# DesignPCB.net
KiCad netlist of a schematic drawn in EasyEDA
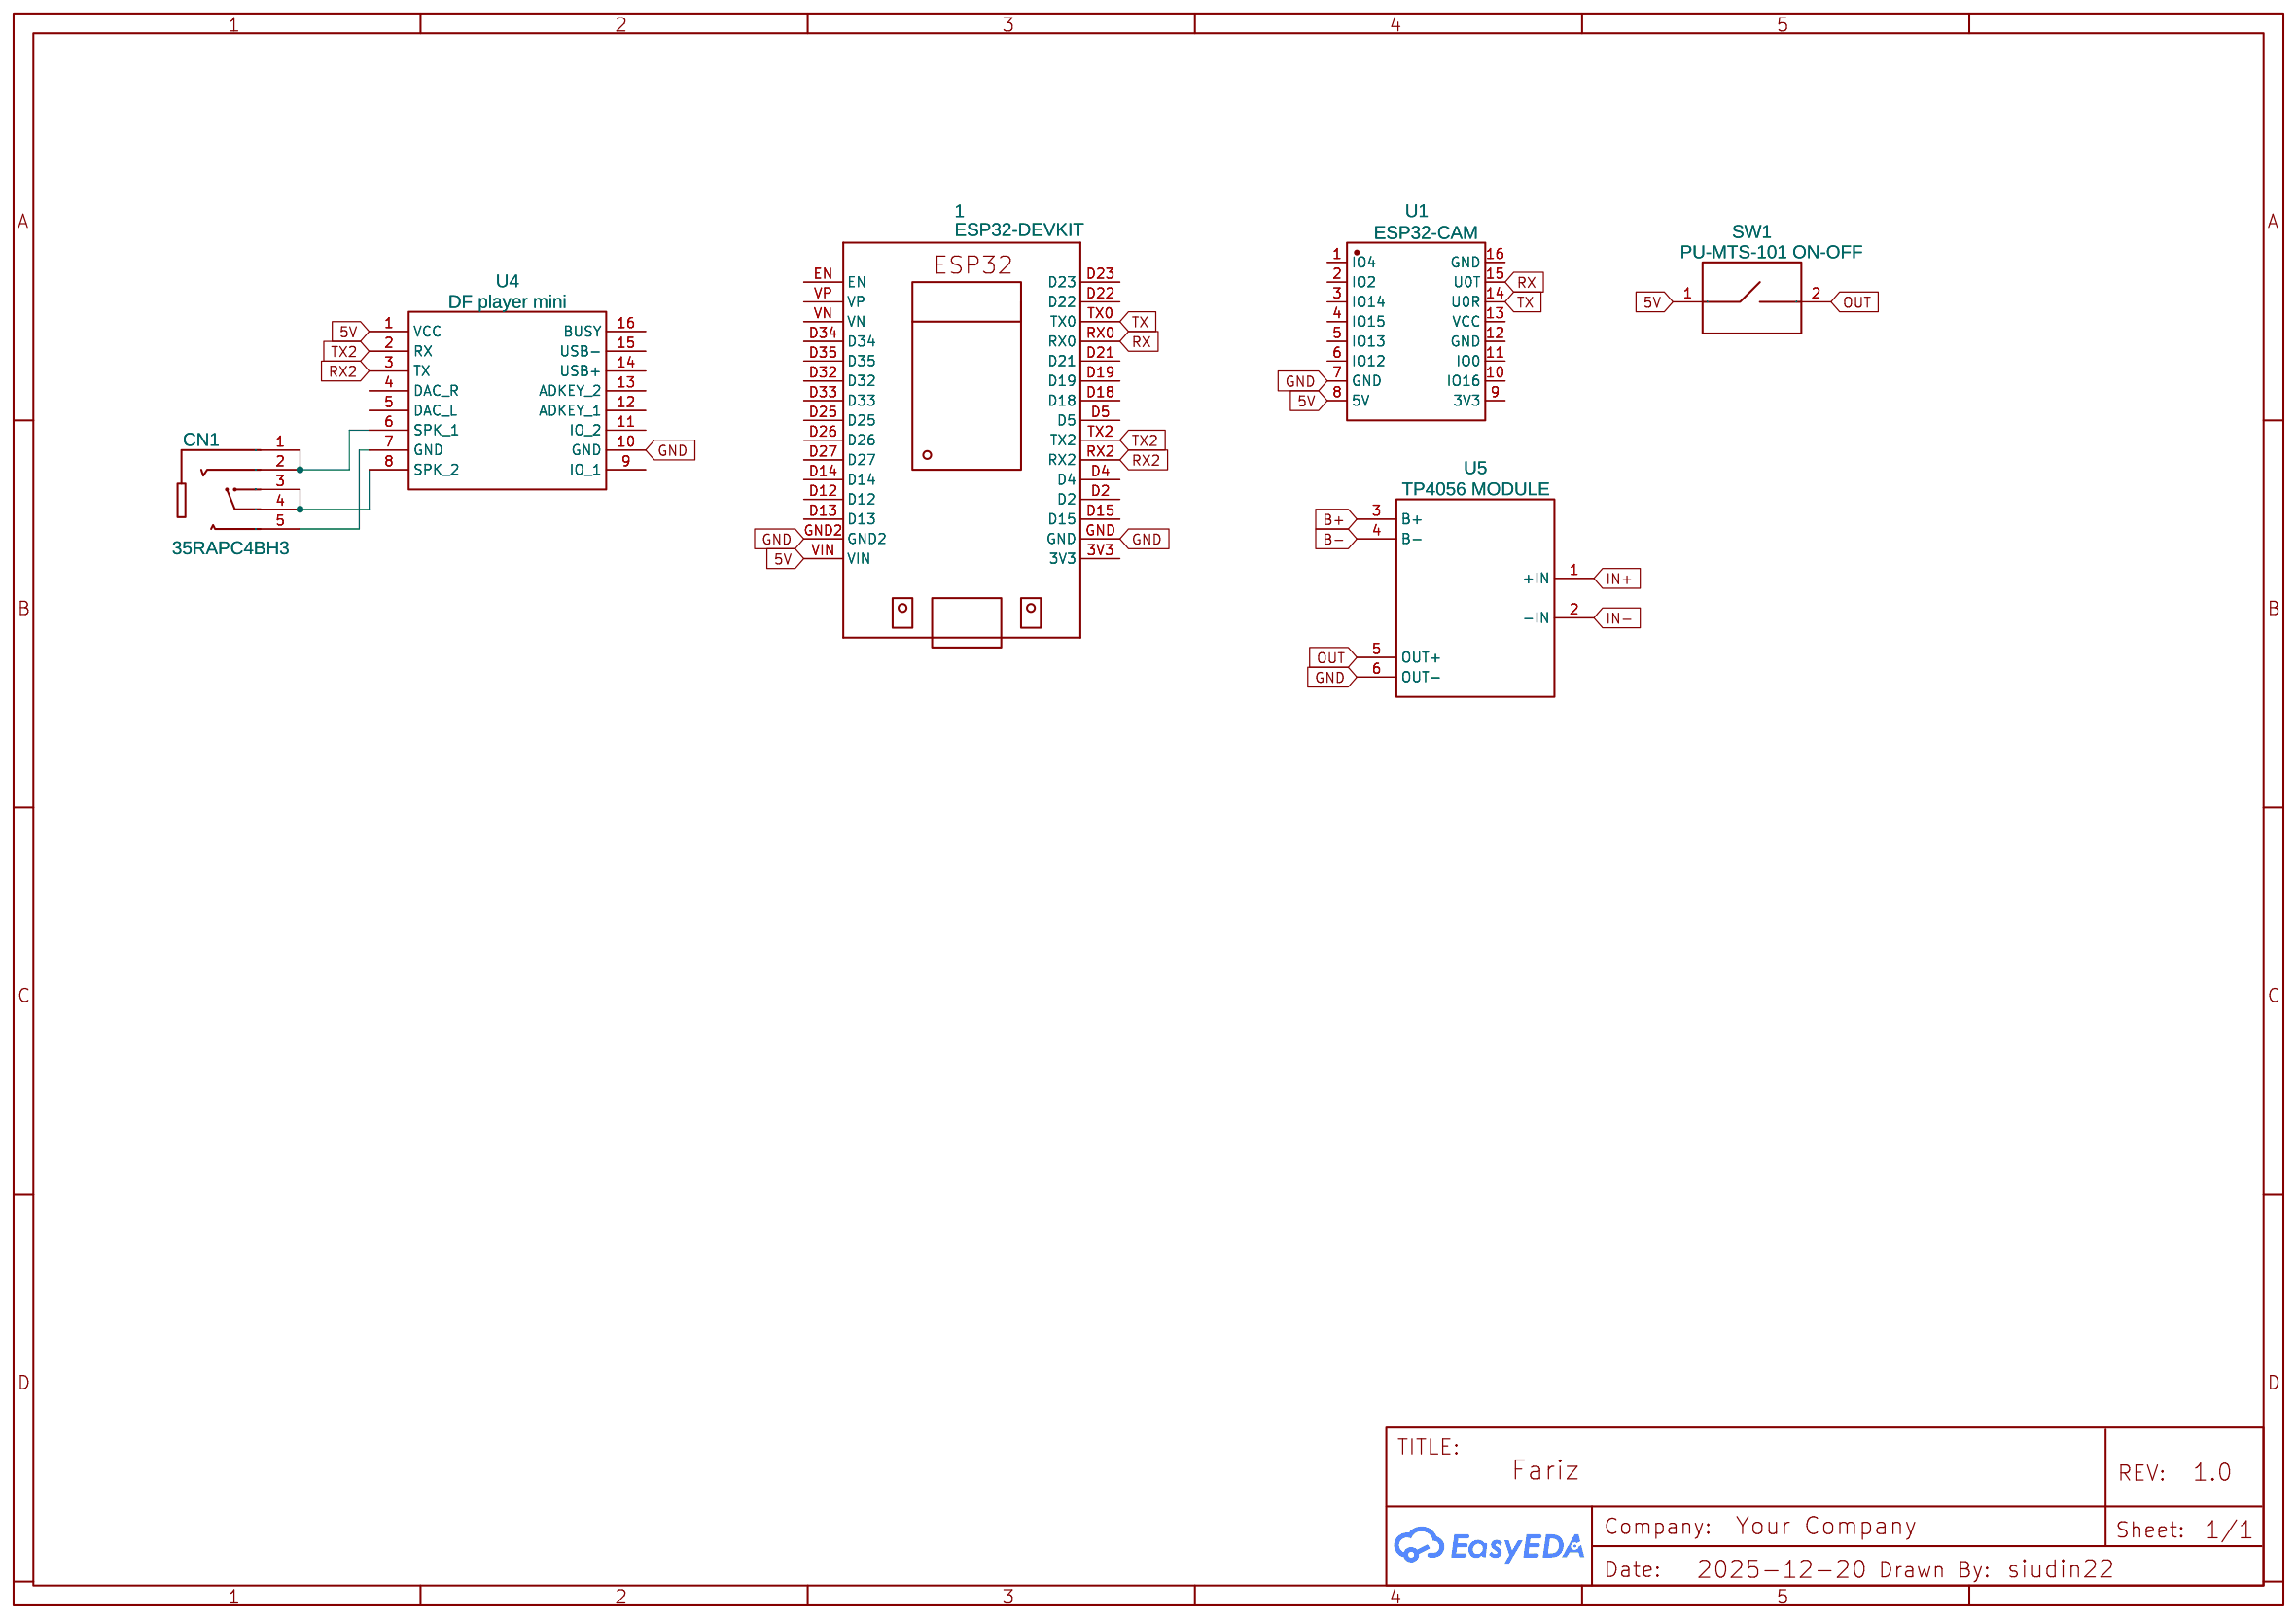
[diagram p0: schematic sheet]

(export (version "E")
  (design (tool "Eeschema 10.0.6"))
  (components
    (comp (ref "1") (value "ESP32-DEVKIT") (libsource (lib "") (part "ESP32-DEVKIT-V1-30PIN")))
    (comp (ref "CN1")
      (value "35RAPC4BH3")
      (fields (field (name "Manufacturer") "Switchcraft"))
      (libsource (lib "") (part "35RAPC4BH3"))
    )
    (comp (ref "SW1")
      (value "PU-MTS-101 ON-OFF")
      (fields (field (name "Manufacturer Part") "pu-mts-101 ON-OFF"))
      (libsource (lib "") (part "PU-MTS-101 ON-OFF"))
    )
    (comp (ref "U1")
      (value "ESP32-CAM")
      (fields (field (name "Manufacturer") "Ai-Thinker(安信可)"))
      (libsource (lib "") (part "ESP32-CAM"))
    )
    (comp (ref "U4") (value "DF player mini") (libsource (lib "") (part "DF player mini")))
    (comp (ref "U5") (value "TP4056 MODULE") (libsource (lib "") (part "TP4056 MODULE")))
  )
  (nets
    (net (code "1") (name "5V") (class "Default")
      (node (ref "1") (pin "VIN") (pinfunction "VIN_VIN") (pintype "unspecified"))
      (node (ref "SW1") (pin "1") (pinfunction "1_1") (pintype "unspecified"))
      (node (ref "U1") (pin "8") (pinfunction "5V_8") (pintype "unspecified"))
      (node (ref "U4") (pin "1") (pinfunction "VCC_1") (pintype "unspecified"))
    )
    (net (code "2") (name "B+") (class "Default")
      (node (ref "U5") (pin "3") (pinfunction "B+_3") (pintype "unspecified"))
    )
    (net (code "3") (name "B-") (class "Default")
      (node (ref "U5") (pin "4") (pinfunction "B-_4") (pintype "unspecified"))
    )
    (net (code "4") (name "GND") (class "Default")
      (node (ref "1") (pin "GND") (pinfunction "GND_GND") (pintype "unspecified"))
      (node (ref "1") (pin "GND2") (pinfunction "GND2_GND2") (pintype "unspecified"))
      (node (ref "U1") (pin "7") (pinfunction "GND_7") (pintype "unspecified"))
      (node (ref "U4") (pin "10") (pinfunction "GND_10") (pintype "unspecified"))
      (node (ref "U5") (pin "6") (pinfunction "OUT-_6") (pintype "unspecified"))
    )
    (net (code "5") (name "IN+") (class "Default")
      (node (ref "U5") (pin "1") (pinfunction "+IN_1") (pintype "unspecified"))
    )
    (net (code "6") (name "IN-") (class "Default")
      (node (ref "U5") (pin "2") (pinfunction "-IN_2") (pintype "unspecified"))
    )
    (net (code "7") (name "Net-(CN1-Pad5)") (class "Default")
      (node (ref "CN1") (pin "5") (pinfunction "5_5") (pintype "unspecified"))
      (node (ref "U4") (pin "7") (pinfunction "GND_7") (pintype "unspecified"))
    )
    (net (code "8") (name "Net-(U4-SPK_1)") (class "Default")
      (node (ref "CN1") (pin "1") (pinfunction "1_1") (pintype "unspecified"))
      (node (ref "CN1") (pin "2") (pinfunction "2_2") (pintype "unspecified"))
      (node (ref "U4") (pin "6") (pinfunction "SPK_1_6") (pintype "unspecified"))
    )
    (net (code "9") (name "Net-(U4-SPK_2)") (class "Default")
      (node (ref "CN1") (pin "3") (pinfunction "3_3") (pintype "unspecified"))
      (node (ref "CN1") (pin "4") (pinfunction "4_4") (pintype "unspecified"))
      (node (ref "U4") (pin "8") (pinfunction "SPK_2_8") (pintype "unspecified"))
    )
    (net (code "10") (name "OUT") (class "Default")
      (node (ref "SW1") (pin "2") (pinfunction "2_2") (pintype "unspecified"))
      (node (ref "U5") (pin "5") (pinfunction "OUT+_5") (pintype "unspecified"))
    )
    (net (code "11") (name "RX") (class "Default")
      (node (ref "1") (pin "RX0") (pinfunction "RX0_RX0") (pintype "unspecified"))
      (node (ref "U1") (pin "15") (pinfunction "U0T_15") (pintype "unspecified"))
    )
    (net (code "12") (name "RX2") (class "Default")
      (node (ref "1") (pin "RX2") (pinfunction "RX2_RX2") (pintype "unspecified"))
      (node (ref "U4") (pin "3") (pinfunction "TX_3") (pintype "unspecified"))
    )
    (net (code "13") (name "TX") (class "Default")
      (node (ref "1") (pin "TX0") (pinfunction "TX0_TX0") (pintype "unspecified"))
      (node (ref "U1") (pin "14") (pinfunction "U0R_14") (pintype "unspecified"))
    )
    (net (code "14") (name "TX2") (class "Default")
      (node (ref "1") (pin "TX2") (pinfunction "TX2_TX2") (pintype "unspecified"))
      (node (ref "U4") (pin "2") (pinfunction "RX_2") (pintype "unspecified"))
    )
    (net (code "15") (name "unconnected-(1-Pad3V3)") (class "Default")
      (node (ref "1") (pin "3V3") (pinfunction "3V3_3V3") (pintype "unspecified"))
    )
    (net (code "16") (name "unconnected-(1-PadD2)") (class "Default")
      (node (ref "1") (pin "D2") (pinfunction "D2_D2") (pintype "unspecified"))
    )
    (net (code "17") (name "unconnected-(1-PadD4)") (class "Default")
      (node (ref "1") (pin "D4") (pinfunction "D4_D4") (pintype "unspecified"))
    )
    (net (code "18") (name "unconnected-(1-PadD5)") (class "Default")
      (node (ref "1") (pin "D5") (pinfunction "D5_D5") (pintype "unspecified"))
    )
    (net (code "19") (name "unconnected-(1-PadD12)") (class "Default")
      (node (ref "1") (pin "D12") (pinfunction "D12_D12") (pintype "unspecified"))
    )
    (net (code "20") (name "unconnected-(1-PadD13)") (class "Default")
      (node (ref "1") (pin "D13") (pinfunction "D13_D13") (pintype "unspecified"))
    )
    (net (code "21") (name "unconnected-(1-PadD14)") (class "Default")
      (node (ref "1") (pin "D14") (pinfunction "D14_D14") (pintype "unspecified"))
    )
    (net (code "22") (name "unconnected-(1-PadD15)") (class "Default")
      (node (ref "1") (pin "D15") (pinfunction "D15_D15") (pintype "unspecified"))
    )
    (net (code "23") (name "unconnected-(1-PadD18)") (class "Default")
      (node (ref "1") (pin "D18") (pinfunction "D18_D18") (pintype "unspecified"))
    )
    (net (code "24") (name "unconnected-(1-PadD19)") (class "Default")
      (node (ref "1") (pin "D19") (pinfunction "D19_D19") (pintype "unspecified"))
    )
    (net (code "25") (name "unconnected-(1-PadD21)") (class "Default")
      (node (ref "1") (pin "D21") (pinfunction "D21_D21") (pintype "unspecified"))
    )
    (net (code "26") (name "unconnected-(1-PadD22)") (class "Default")
      (node (ref "1") (pin "D22") (pinfunction "D22_D22") (pintype "unspecified"))
    )
    (net (code "27") (name "unconnected-(1-PadD23)") (class "Default")
      (node (ref "1") (pin "D23") (pinfunction "D23_D23") (pintype "unspecified"))
    )
    (net (code "28") (name "unconnected-(1-PadD25)") (class "Default")
      (node (ref "1") (pin "D25") (pinfunction "D25_D25") (pintype "unspecified"))
    )
    (net (code "29") (name "unconnected-(1-PadD26)") (class "Default")
      (node (ref "1") (pin "D26") (pinfunction "D26_D26") (pintype "unspecified"))
    )
    (net (code "30") (name "unconnected-(1-PadD27)") (class "Default")
      (node (ref "1") (pin "D27") (pinfunction "D27_D27") (pintype "unspecified"))
    )
    (net (code "31") (name "unconnected-(1-PadD32)") (class "Default")
      (node (ref "1") (pin "D32") (pinfunction "D32_D32") (pintype "unspecified"))
    )
    (net (code "32") (name "unconnected-(1-PadD33)") (class "Default")
      (node (ref "1") (pin "D33") (pinfunction "D33_D33") (pintype "unspecified"))
    )
    (net (code "33") (name "unconnected-(1-PadD34)") (class "Default")
      (node (ref "1") (pin "D34") (pinfunction "D34_D34") (pintype "unspecified"))
    )
    (net (code "34") (name "unconnected-(1-PadD35)") (class "Default")
      (node (ref "1") (pin "D35") (pinfunction "D35_D35") (pintype "unspecified"))
    )
    (net (code "35") (name "unconnected-(1-PadEN)") (class "Default")
      (node (ref "1") (pin "EN") (pinfunction "EN_EN") (pintype "unspecified"))
    )
    (net (code "36") (name "unconnected-(1-PadVN)") (class "Default")
      (node (ref "1") (pin "VN") (pinfunction "VN_VN") (pintype "unspecified"))
    )
    (net (code "37") (name "unconnected-(1-PadVP)") (class "Default")
      (node (ref "1") (pin "VP") (pinfunction "VP_VP") (pintype "unspecified"))
    )
    (net (code "38") (name "unconnected-(U1-3V3-Pad9)") (class "Default")
      (node (ref "U1") (pin "9") (pinfunction "3V3_9") (pintype "unspecified"))
    )
    (net (code "39") (name "unconnected-(U1-GND-Pad12)") (class "Default")
      (node (ref "U1") (pin "12") (pinfunction "GND_12") (pintype "unspecified"))
    )
    (net (code "40") (name "unconnected-(U1-GND-Pad16)") (class "Default")
      (node (ref "U1") (pin "16") (pinfunction "GND_16") (pintype "unspecified"))
    )
    (net (code "41") (name "unconnected-(U1-IO0-Pad11)") (class "Default")
      (node (ref "U1") (pin "11") (pinfunction "IO0_11") (pintype "unspecified"))
    )
    (net (code "42") (name "unconnected-(U1-IO2-Pad2)") (class "Default")
      (node (ref "U1") (pin "2") (pinfunction "IO2_2") (pintype "unspecified"))
    )
    (net (code "43") (name "unconnected-(U1-IO4-Pad1)") (class "Default")
      (node (ref "U1") (pin "1") (pinfunction "IO4_1") (pintype "unspecified"))
    )
    (net (code "44") (name "unconnected-(U1-IO12-Pad6)") (class "Default")
      (node (ref "U1") (pin "6") (pinfunction "IO12_6") (pintype "unspecified"))
    )
    (net (code "45") (name "unconnected-(U1-IO13-Pad5)") (class "Default")
      (node (ref "U1") (pin "5") (pinfunction "IO13_5") (pintype "unspecified"))
    )
    (net (code "46") (name "unconnected-(U1-IO14-Pad3)") (class "Default")
      (node (ref "U1") (pin "3") (pinfunction "IO14_3") (pintype "unspecified"))
    )
    (net (code "47") (name "unconnected-(U1-IO15-Pad4)") (class "Default")
      (node (ref "U1") (pin "4") (pinfunction "IO15_4") (pintype "unspecified"))
    )
    (net (code "48") (name "unconnected-(U1-IO16-Pad10)") (class "Default")
      (node (ref "U1") (pin "10") (pinfunction "IO16_10") (pintype "unspecified"))
    )
    (net (code "49") (name "unconnected-(U1-VCC-Pad13)") (class "Default")
      (node (ref "U1") (pin "13") (pinfunction "VCC_13") (pintype "unspecified"))
    )
    (net (code "50") (name "unconnected-(U4-ADKEY_1-Pad12)") (class "Default")
      (node (ref "U4") (pin "12") (pinfunction "ADKEY_1_12") (pintype "unspecified"))
    )
    (net (code "51") (name "unconnected-(U4-ADKEY_2-Pad13)") (class "Default")
      (node (ref "U4") (pin "13") (pinfunction "ADKEY_2_13") (pintype "unspecified"))
    )
    (net (code "52") (name "unconnected-(U4-BUSY-Pad16)") (class "Default")
      (node (ref "U4") (pin "16") (pinfunction "BUSY_16") (pintype "unspecified"))
    )
    (net (code "53") (name "unconnected-(U4-DAC_L-Pad5)") (class "Default")
      (node (ref "U4") (pin "5") (pinfunction "DAC_L_5") (pintype "unspecified"))
    )
    (net (code "54") (name "unconnected-(U4-DAC_R-Pad4)") (class "Default")
      (node (ref "U4") (pin "4") (pinfunction "DAC_R_4") (pintype "unspecified"))
    )
    (net (code "55") (name "unconnected-(U4-IO_1-Pad9)") (class "Default")
      (node (ref "U4") (pin "9") (pinfunction "IO_1_9") (pintype "unspecified"))
    )
    (net (code "56") (name "unconnected-(U4-IO_2-Pad11)") (class "Default")
      (node (ref "U4") (pin "11") (pinfunction "IO_2_11") (pintype "unspecified"))
    )
    (net (code "57") (name "unconnected-(U4-USB+-Pad14)") (class "Default")
      (node (ref "U4") (pin "14") (pinfunction "USB+_14") (pintype "unspecified"))
    )
    (net (code "58") (name "unconnected-(U4-USB--Pad15)") (class "Default")
      (node (ref "U4") (pin "15") (pinfunction "USB-_15") (pintype "unspecified"))
    )
  )
)
